# POWER.net
KiCad netlist of a schematic drawn in Altium Designer
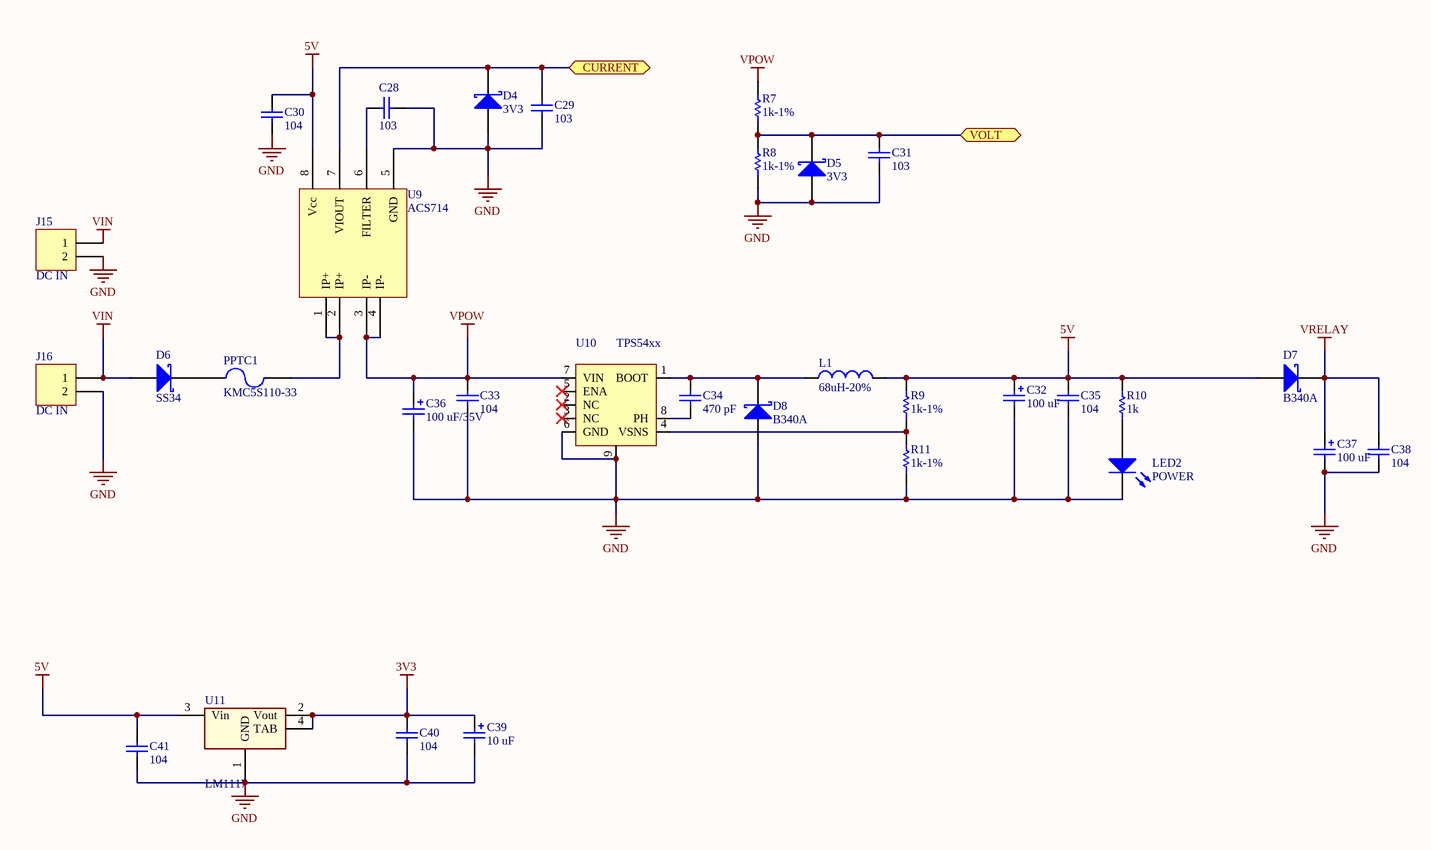
[diagram p0: POWER.SchDoc]

(export (version "E")
  (design (tool "Eeschema 10.0.6"))
  (components
    (comp (ref "C28")
      (value "103")
      (footprint "C0603")
      (description "CAP CER 0.1UF 16V Y5V 0402")
      (fields
        (field (name "MANUFACTURER") "Yageo")
        (field (name "DIGI-KEY PART NUMBER") "311-1047-1-ND")
        (field (name "PUBLISHER") "Altium Limited")
      )
      (libsource (lib "RobotClub") (part "Cap_SMT"))
    )
    (comp (ref "C29")
      (value "103")
      (footprint "C0603")
      (description "CAP CER 0.1UF 16V Y5V 0402")
      (fields
        (field (name "MANUFACTURER") "Yageo")
        (field (name "DIGI-KEY PART NUMBER") "311-1047-1-ND")
        (field (name "PUBLISHER") "Altium Limited")
      )
      (libsource (lib "RobotClub") (part "Cap_SMT"))
    )
    (comp (ref "C30")
      (value "104")
      (footprint "C0603")
      (description "CAP CER 0.1UF 16V Y5V 0402")
      (fields
        (field (name "MANUFACTURER") "Yageo")
        (field (name "DIGI-KEY PART NUMBER") "311-1047-1-ND")
        (field (name "PUBLISHER") "Altium Limited")
      )
      (libsource (lib "RobotClub") (part "Cap_SMT"))
    )
    (comp (ref "C31")
      (value "103")
      (footprint "C0603")
      (description "CAP CER 0.1UF 16V Y5V 0402")
      (fields
        (field (name "MANUFACTURER") "Yageo")
        (field (name "DIGI-KEY PART NUMBER") "311-1047-1-ND")
        (field (name "PUBLISHER") "Altium Limited")
      )
      (libsource (lib "RobotClub") (part "Cap_SMT"))
    )
    (comp (ref "C32")
      (value "100 uF")
      (footprint "CAP_TANTA_SMD_100UF/16V")
      (description "CAP TANTA")
      (libsource (lib "RobotClub") (part "Cap_TANTA"))
    )
    (comp (ref "C33")
      (value "104")
      (footprint "C0603")
      (description "CAP CER 0.1UF 16V Y5V 0402")
      (fields
        (field (name "MANUFACTURER") "Yageo")
        (field (name "DIGI-KEY PART NUMBER") "311-1047-1-ND")
        (field (name "PUBLISHER") "Altium Limited")
      )
      (libsource (lib "RobotClub") (part "Cap_SMT"))
    )
    (comp (ref "C34")
      (value "470 pF")
      (footprint "C0603")
      (description "CAP CER 0.1UF 16V Y5V 0402")
      (fields
        (field (name "MANUFACTURER") "Yageo")
        (field (name "DIGI-KEY PART NUMBER") "311-1047-1-ND")
        (field (name "PUBLISHER") "Altium Limited")
      )
      (libsource (lib "RobotClub") (part "Cap_SMT"))
    )
    (comp (ref "C35")
      (value "104")
      (footprint "C0603")
      (description "CAP CER 0.1UF 16V Y5V 0402")
      (fields
        (field (name "MANUFACTURER") "Yageo")
        (field (name "DIGI-KEY PART NUMBER") "311-1047-1-ND")
        (field (name "PUBLISHER") "Altium Limited")
      )
      (libsource (lib "RobotClub") (part "Cap_SMT"))
    )
    (comp (ref "C36")
      (value "100 uF/35V")
      (footprint "CAP_AL_SMD (10X10.2)")
      (description "CAP ALU")
      (libsource (lib "RobotClub") (part "Cap_ALU"))
    )
    (comp (ref "C37")
      (value "100 uF")
      (footprint "CAP_TANTA_SMD_100UF/16V")
      (description "CAP TANTA")
      (libsource (lib "RobotClub") (part "Cap_TANTA"))
    )
    (comp (ref "C38")
      (value "104")
      (footprint "C0603")
      (description "CAP CER 0.1UF 16V Y5V 0402")
      (fields
        (field (name "MANUFACTURER") "Yageo")
        (field (name "DIGI-KEY PART NUMBER") "311-1047-1-ND")
        (field (name "PUBLISHER") "Altium Limited")
      )
      (libsource (lib "RobotClub") (part "Cap_SMT"))
    )
    (comp (ref "C39")
      (value "10 uF")
      (footprint "CAP_TANTA_SMD_100UF/16V")
      (description "CAP TANTA")
      (libsource (lib "RobotClub") (part "Cap_TANTA"))
    )
    (comp (ref "C40")
      (value "104")
      (footprint "C0603")
      (description "CAP CER 0.1UF 16V Y5V 0402")
      (fields
        (field (name "MANUFACTURER") "Yageo")
        (field (name "DIGI-KEY PART NUMBER") "311-1047-1-ND")
        (field (name "PUBLISHER") "Altium Limited")
      )
      (libsource (lib "RobotClub") (part "Cap_SMT"))
    )
    (comp (ref "C41")
      (value "104")
      (footprint "C0603")
      (description "CAP CER 0.1UF 16V Y5V 0402")
      (fields
        (field (name "MANUFACTURER") "Yageo")
        (field (name "DIGI-KEY PART NUMBER") "311-1047-1-ND")
        (field (name "PUBLISHER") "Altium Limited")
      )
      (libsource (lib "RobotClub") (part "Cap_SMT"))
    )
    (comp (ref "D4")
      (value "3V3")
      (footprint "DO_213AA")
      (description "DIODE SCHOTTKY 40V 3A SMA")
      (fields
        (field (name "DIGI-KEY PART NUMBER") "B340A-E3/61TGITR-ND")
        (field (name "MANUFACTURER PART NUMBER") "B340A-E3/61T")
        (field (name "PUBLISHER") "Altium Limited")
      )
      (libsource (lib "RobotClub") (part "D Schottky"))
    )
    (comp (ref "D5")
      (value "3V3")
      (footprint "DO_213AA")
      (description "DIODE SCHOTTKY 40V 3A SMA")
      (fields
        (field (name "DIGI-KEY PART NUMBER") "B340A-E3/61TGITR-ND")
        (field (name "MANUFACTURER PART NUMBER") "B340A-E3/61T")
        (field (name "PUBLISHER") "Altium Limited")
      )
      (libsource (lib "RobotClub") (part "D Schottky"))
    )
    (comp (ref "D6")
      (value "SS34")
      (footprint "DO-214AC (SMA)")
      (description "DIODE SCHOTTKY 40V 3A SMA")
      (fields
        (field (name "DIGI-KEY PART NUMBER") "B340A-E3/61TGITR-ND")
        (field (name "MANUFACTURER PART NUMBER") "B340A-E3/61T")
        (field (name "PUBLISHER") "Altium Limited")
      )
      (libsource (lib "RobotClub") (part "D Schottky"))
    )
    (comp (ref "D7")
      (value "B340A")
      (footprint "DO-214AC (SMA)")
      (description "DIODE SCHOTTKY 40V 3A SMA")
      (fields
        (field (name "DIGI-KEY PART NUMBER") "B340A-E3/61TGITR-ND")
        (field (name "MANUFACTURER PART NUMBER") "B340A-E3/61T")
        (field (name "PUBLISHER") "Altium Limited")
      )
      (libsource (lib "RobotClub") (part "D Schottky"))
    )
    (comp (ref "D8")
      (value "B340A")
      (footprint "DO-214AC (SMA)")
      (description "DIODE SCHOTTKY 40V 3A SMA")
      (fields
        (field (name "DIGI-KEY PART NUMBER") "B340A-E3/61TGITR-ND")
        (field (name "MANUFACTURER PART NUMBER") "B340A-E3/61T")
        (field (name "PUBLISHER") "Altium Limited")
      )
      (libsource (lib "RobotClub") (part "D Schottky"))
    )
    (comp (ref "J15")
      (value "DC IN")
      (footprint "DOMINO NORMAL 2")
      (description "Header, 2-Pin")
      (fields (field (name "PUBLISHER") "Altium Limited"))
      (libsource (lib "RobotClub") (part "Header 2"))
    )
    (comp (ref "J16")
      (value "DC IN")
      (footprint "DOMINO NORMAL 2")
      (description "Header, 2-Pin")
      (fields (field (name "PUBLISHER") "Altium Limited"))
      (libsource (lib "RobotClub") (part "Header 2"))
    )
    (comp (ref "L1")
      (value "68uH-20%")
      (footprint "L10.4W10.4H4.8")
      (description "INDUCTOR POWER 68UH SMD")
      (fields
        (field (name "DIGI-KEY PART NUMBER") "ASPI-6045S-680M-TTR-ND")
        (field (name "MANUFACTURER") "Abracon Corporation")
        (field (name "PUBLISHER") "Altium Limited")
      )
      (libsource (lib "RobotClub") (part "Inductor"))
    )
    (comp (ref "LED2")
      (value "POWER")
      (footprint "SM/LED_0603")
      (description "LED GREEN 0.2MM 13MCD 0402 SMD")
      (fields
        (field (name "DIGI-KEY PART NUMBER") "511-1592-2-ND")
        (field (name "MANUFACTURER") "Lite-On Inc")
        (field (name "PUBLISHER") "Altium Limited")
      )
      (libsource (lib "RobotClub") (part "LED"))
    )
    (comp (ref "PPTC1")
      (value "KMC5S110-33")
      (footprint "PTC1812")
      (description "POLYSWITCH .50A RESET FUSE SMD")
      (fields
        (field (name "DIGI-KEY PART NUMBER") "MINISMDC050FCT-ND")
        (field (name "MANUFACTURER") "TE Connectivity")
        (field (name "PUBLISHER") "Altium Limited")
      )
      (libsource (lib "RobotClub") (part "Fuse 2"))
    )
    (comp (ref "R7")
      (value "1k-1%")
      (footprint "R0603")
      (description "Resistor SMD 1%")
      (fields
        (field (name "DIGI-KEY PART NUMBER") "P3.24KLTR-ND")
        (field (name "MANUFACTURER") "Panasonic Electronic Components")
        (field (name "PUBLISHER") "Altium Limited")
      )
      (libsource (lib "RobotClub") (part "R_SMD1"))
    )
    (comp (ref "R8")
      (value "1k-1%")
      (footprint "R0603")
      (description "Resistor SMD 1%")
      (fields
        (field (name "DIGI-KEY PART NUMBER") "P3.24KLTR-ND")
        (field (name "MANUFACTURER") "Panasonic Electronic Components")
        (field (name "PUBLISHER") "Altium Limited")
      )
      (libsource (lib "RobotClub") (part "R_SMD1"))
    )
    (comp (ref "R9")
      (value "1k-1%")
      (footprint "R0603")
      (description "Resistor SMD 1%")
      (fields
        (field (name "DIGI-KEY PART NUMBER") "P3.24KLTR-ND")
        (field (name "MANUFACTURER") "Panasonic Electronic Components")
        (field (name "PUBLISHER") "Altium Limited")
      )
      (libsource (lib "RobotClub") (part "R_SMD1"))
    )
    (comp (ref "R10")
      (value "1k")
      (footprint "R0603")
      (description "Resistor SMD 5%")
      (fields
        (field (name "DIGI-KEY PART NUMBER") "P3.24KLTR-ND")
        (field (name "MANUFACTURER") "Panasonic Electronic Components")
        (field (name "PUBLISHER") "Altium Limited")
      )
      (libsource (lib "RobotClub") (part "R_SMD5"))
    )
    (comp (ref "R11")
      (value "1k-1%")
      (footprint "R0603")
      (description "Resistor SMD 1%")
      (fields
        (field (name "DIGI-KEY PART NUMBER") "P3.24KLTR-ND")
        (field (name "MANUFACTURER") "Panasonic Electronic Components")
        (field (name "PUBLISHER") "Altium Limited")
      )
      (libsource (lib "RobotClub") (part "R_SMD1"))
    )
    (comp (ref "U9")
      (value "ACS714")
      (footprint "SOIC-8N")
      (description "AutomotiveHall Effect-Based Linear Current Sensor")
      (libsource (lib "RobotClub") (part "ACS714"))
    )
    (comp (ref "U10")
      (value "TPS54xx")
      (footprint "HSOIOCN")
      (description "IC REG BUCK ADJ 1A 8SOIC")
      (fields
        (field (name "DIGI-KEY PART NUMBER") "296-26988-2-ND")
        (field (name "MANUFACTURER") "Texas Instruments")
      )
      (libsource (lib "RobotClub") (part "TPS54xx"))
    )
    (comp (ref "U11") (value "LM1117") (footprint "SOT223_L") (libsource (lib "RobotClub") (part "LM1117")))
  )
  (nets
    (net (code "1") (name "/CURRENT") (class "Default")
      (node (ref "C29") (pin "2") (pinfunction "2_2") (pintype "passive"))
      (node (ref "D4") (pin "2") (pinfunction "K_2") (pintype "passive"))
      (node (ref "U9") (pin "7") (pinfunction "VIOUT_7") (pintype "passive"))
    )
    (net (code "2") (name "/VOLT") (class "Default")
      (node (ref "C31") (pin "2") (pinfunction "2_2") (pintype "passive"))
      (node (ref "D5") (pin "2") (pinfunction "K_2") (pintype "passive"))
      (node (ref "R7") (pin "1") (pinfunction "1_1") (pintype "passive"))
      (node (ref "R8") (pin "2") (pinfunction "2_2") (pintype "passive"))
    )
    (net (code "3") (name "3V3") (class "Default")
      (node (ref "C39") (pin "1") (pinfunction "1_1") (pintype "passive"))
      (node (ref "C40") (pin "2") (pinfunction "2_2") (pintype "passive"))
      (node (ref "U11") (pin "2") (pinfunction "Vout_2") (pintype "passive"))
      (node (ref "U11") (pin "4") (pinfunction "TAB_4") (pintype "passive"))
    )
    (net (code "4") (name "5V") (class "Default")
      (node (ref "C30") (pin "2") (pinfunction "2_2") (pintype "passive"))
      (node (ref "C32") (pin "1") (pinfunction "1_1") (pintype "passive"))
      (node (ref "C35") (pin "2") (pinfunction "2_2") (pintype "passive"))
      (node (ref "C41") (pin "2") (pinfunction "2_2") (pintype "passive"))
      (node (ref "D7") (pin "1") (pinfunction "A_1") (pintype "passive"))
      (node (ref "L1") (pin "2") (pinfunction "2_2") (pintype "passive"))
      (node (ref "R10") (pin "2") (pinfunction "2_2") (pintype "passive"))
      (node (ref "R9") (pin "2") (pinfunction "2_2") (pintype "passive"))
      (node (ref "U11") (pin "3") (pinfunction "Vin_3") (pintype "passive"))
      (node (ref "U9") (pin "8") (pinfunction "Vcc_8") (pintype "passive"))
    )
    (net (code "5") (name "GND") (class "Default")
      (node (ref "C28") (pin "1") (pinfunction "1_1") (pintype "passive"))
      (node (ref "C29") (pin "1") (pinfunction "1_1") (pintype "passive"))
      (node (ref "C30") (pin "1") (pinfunction "1_1") (pintype "passive"))
      (node (ref "C31") (pin "1") (pinfunction "1_1") (pintype "passive"))
      (node (ref "C32") (pin "2") (pinfunction "2_2") (pintype "passive"))
      (node (ref "C33") (pin "2") (pinfunction "2_2") (pintype "passive"))
      (node (ref "C35") (pin "1") (pinfunction "1_1") (pintype "passive"))
      (node (ref "C36") (pin "2") (pinfunction "2_2") (pintype "passive"))
      (node (ref "C37") (pin "2") (pinfunction "2_2") (pintype "passive"))
      (node (ref "C38") (pin "1") (pinfunction "1_1") (pintype "passive"))
      (node (ref "C39") (pin "2") (pinfunction "2_2") (pintype "passive"))
      (node (ref "C40") (pin "1") (pinfunction "1_1") (pintype "passive"))
      (node (ref "C41") (pin "1") (pinfunction "1_1") (pintype "passive"))
      (node (ref "D4") (pin "1") (pinfunction "A_1") (pintype "passive"))
      (node (ref "D5") (pin "1") (pinfunction "A_1") (pintype "passive"))
      (node (ref "D8") (pin "1") (pinfunction "A_1") (pintype "passive"))
      (node (ref "J15") (pin "2") (pinfunction "2_2") (pintype "passive"))
      (node (ref "J16") (pin "2") (pinfunction "2_2") (pintype "passive"))
      (node (ref "LED2") (pin "2") (pinfunction "K_2") (pintype "passive"))
      (node (ref "R11") (pin "1") (pinfunction "1_1") (pintype "passive"))
      (node (ref "R8") (pin "1") (pinfunction "1_1") (pintype "passive"))
      (node (ref "U10") (pin "6") (pinfunction "GND_6") (pintype "passive"))
      (node (ref "U10") (pin "9") (pinfunction "G-PAD_9") (pintype "passive"))
      (node (ref "U11") (pin "1") (pinfunction "GND_1") (pintype "passive"))
      (node (ref "U9") (pin "5") (pinfunction "GND_5") (pintype "passive"))
    )
    (net (code "6") (name "Net-(D6-K)") (class "Default")
      (node (ref "D6") (pin "2") (pinfunction "K_2") (pintype "passive"))
      (node (ref "PPTC1") (pin "1") (pinfunction "1_1") (pintype "passive"))
    )
    (net (code "7") (name "Net-(D8-K)") (class "Default")
      (node (ref "C34") (pin "2") (pinfunction "2_2") (pintype "passive"))
      (node (ref "D8") (pin "2") (pinfunction "K_2") (pintype "passive"))
      (node (ref "L1") (pin "1") (pinfunction "1_1") (pintype "passive"))
      (node (ref "U10") (pin "1") (pinfunction "BOOT_1") (pintype "passive"))
    )
    (net (code "8") (name "Net-(LED2-A)") (class "Default")
      (node (ref "LED2") (pin "1") (pinfunction "A_1") (pintype "passive"))
      (node (ref "R10") (pin "1") (pinfunction "1_1") (pintype "passive"))
    )
    (net (code "9") (name "Net-(PPTC1-Pad2)") (class "Default")
      (node (ref "PPTC1") (pin "2") (pinfunction "2_2") (pintype "passive"))
      (node (ref "U9") (pin "1") (pinfunction "IP+_1") (pintype "passive"))
      (node (ref "U9") (pin "2") (pinfunction "IP+_2") (pintype "passive"))
    )
    (net (code "10") (name "Net-(U9-FILTER)") (class "Default")
      (node (ref "C28") (pin "2") (pinfunction "2_2") (pintype "passive"))
      (node (ref "U9") (pin "6") (pinfunction "FILTER_6") (pintype "passive"))
    )
    (net (code "11") (name "Net-(U10-PH)") (class "Default")
      (node (ref "C34") (pin "1") (pinfunction "1_1") (pintype "passive"))
      (node (ref "U10") (pin "8") (pinfunction "PH_8") (pintype "passive"))
    )
    (net (code "12") (name "Net-(U10-VSNS)") (class "Default")
      (node (ref "R11") (pin "2") (pinfunction "2_2") (pintype "passive"))
      (node (ref "R9") (pin "1") (pinfunction "1_1") (pintype "passive"))
      (node (ref "U10") (pin "4") (pinfunction "VSNS_4") (pintype "passive"))
    )
    (net (code "13") (name "VIN") (class "Default")
      (node (ref "D6") (pin "1") (pinfunction "A_1") (pintype "passive"))
      (node (ref "J15") (pin "1") (pinfunction "1_1") (pintype "passive"))
      (node (ref "J16") (pin "1") (pinfunction "1_1") (pintype "passive"))
    )
    (net (code "14") (name "VPOW") (class "Default")
      (node (ref "C33") (pin "1") (pinfunction "1_1") (pintype "passive"))
      (node (ref "C36") (pin "1") (pinfunction "1_1") (pintype "passive"))
      (node (ref "R7") (pin "2") (pinfunction "2_2") (pintype "passive"))
      (node (ref "U10") (pin "7") (pinfunction "VIN_7") (pintype "passive"))
      (node (ref "U9") (pin "3") (pinfunction "IP-_3") (pintype "passive"))
      (node (ref "U9") (pin "4") (pinfunction "IP-_4") (pintype "passive"))
    )
    (net (code "15") (name "VRELAY") (class "Default")
      (node (ref "C37") (pin "1") (pinfunction "1_1") (pintype "passive"))
      (node (ref "C38") (pin "2") (pinfunction "2_2") (pintype "passive"))
      (node (ref "D7") (pin "2") (pinfunction "K_2") (pintype "passive"))
    )
    (net (code "16") (name "unconnected-(U10-ENA-Pad5)") (class "Default")
      (node (ref "U10") (pin "5") (pinfunction "ENA_5") (pintype "passive+no_connect"))
    )
    (net (code "17") (name "unconnected-(U10-NC-Pad2)") (class "Default")
      (node (ref "U10") (pin "2") (pinfunction "NC_2") (pintype "passive+no_connect"))
    )
    (net (code "18") (name "unconnected-(U10-NC-Pad3)") (class "Default")
      (node (ref "U10") (pin "3") (pinfunction "NC_3") (pintype "passive+no_connect"))
    )
  )
)
